# Ada_-_V1_as_built.net
KiCad netlist of a schematic drawn in EasyEDA Pro
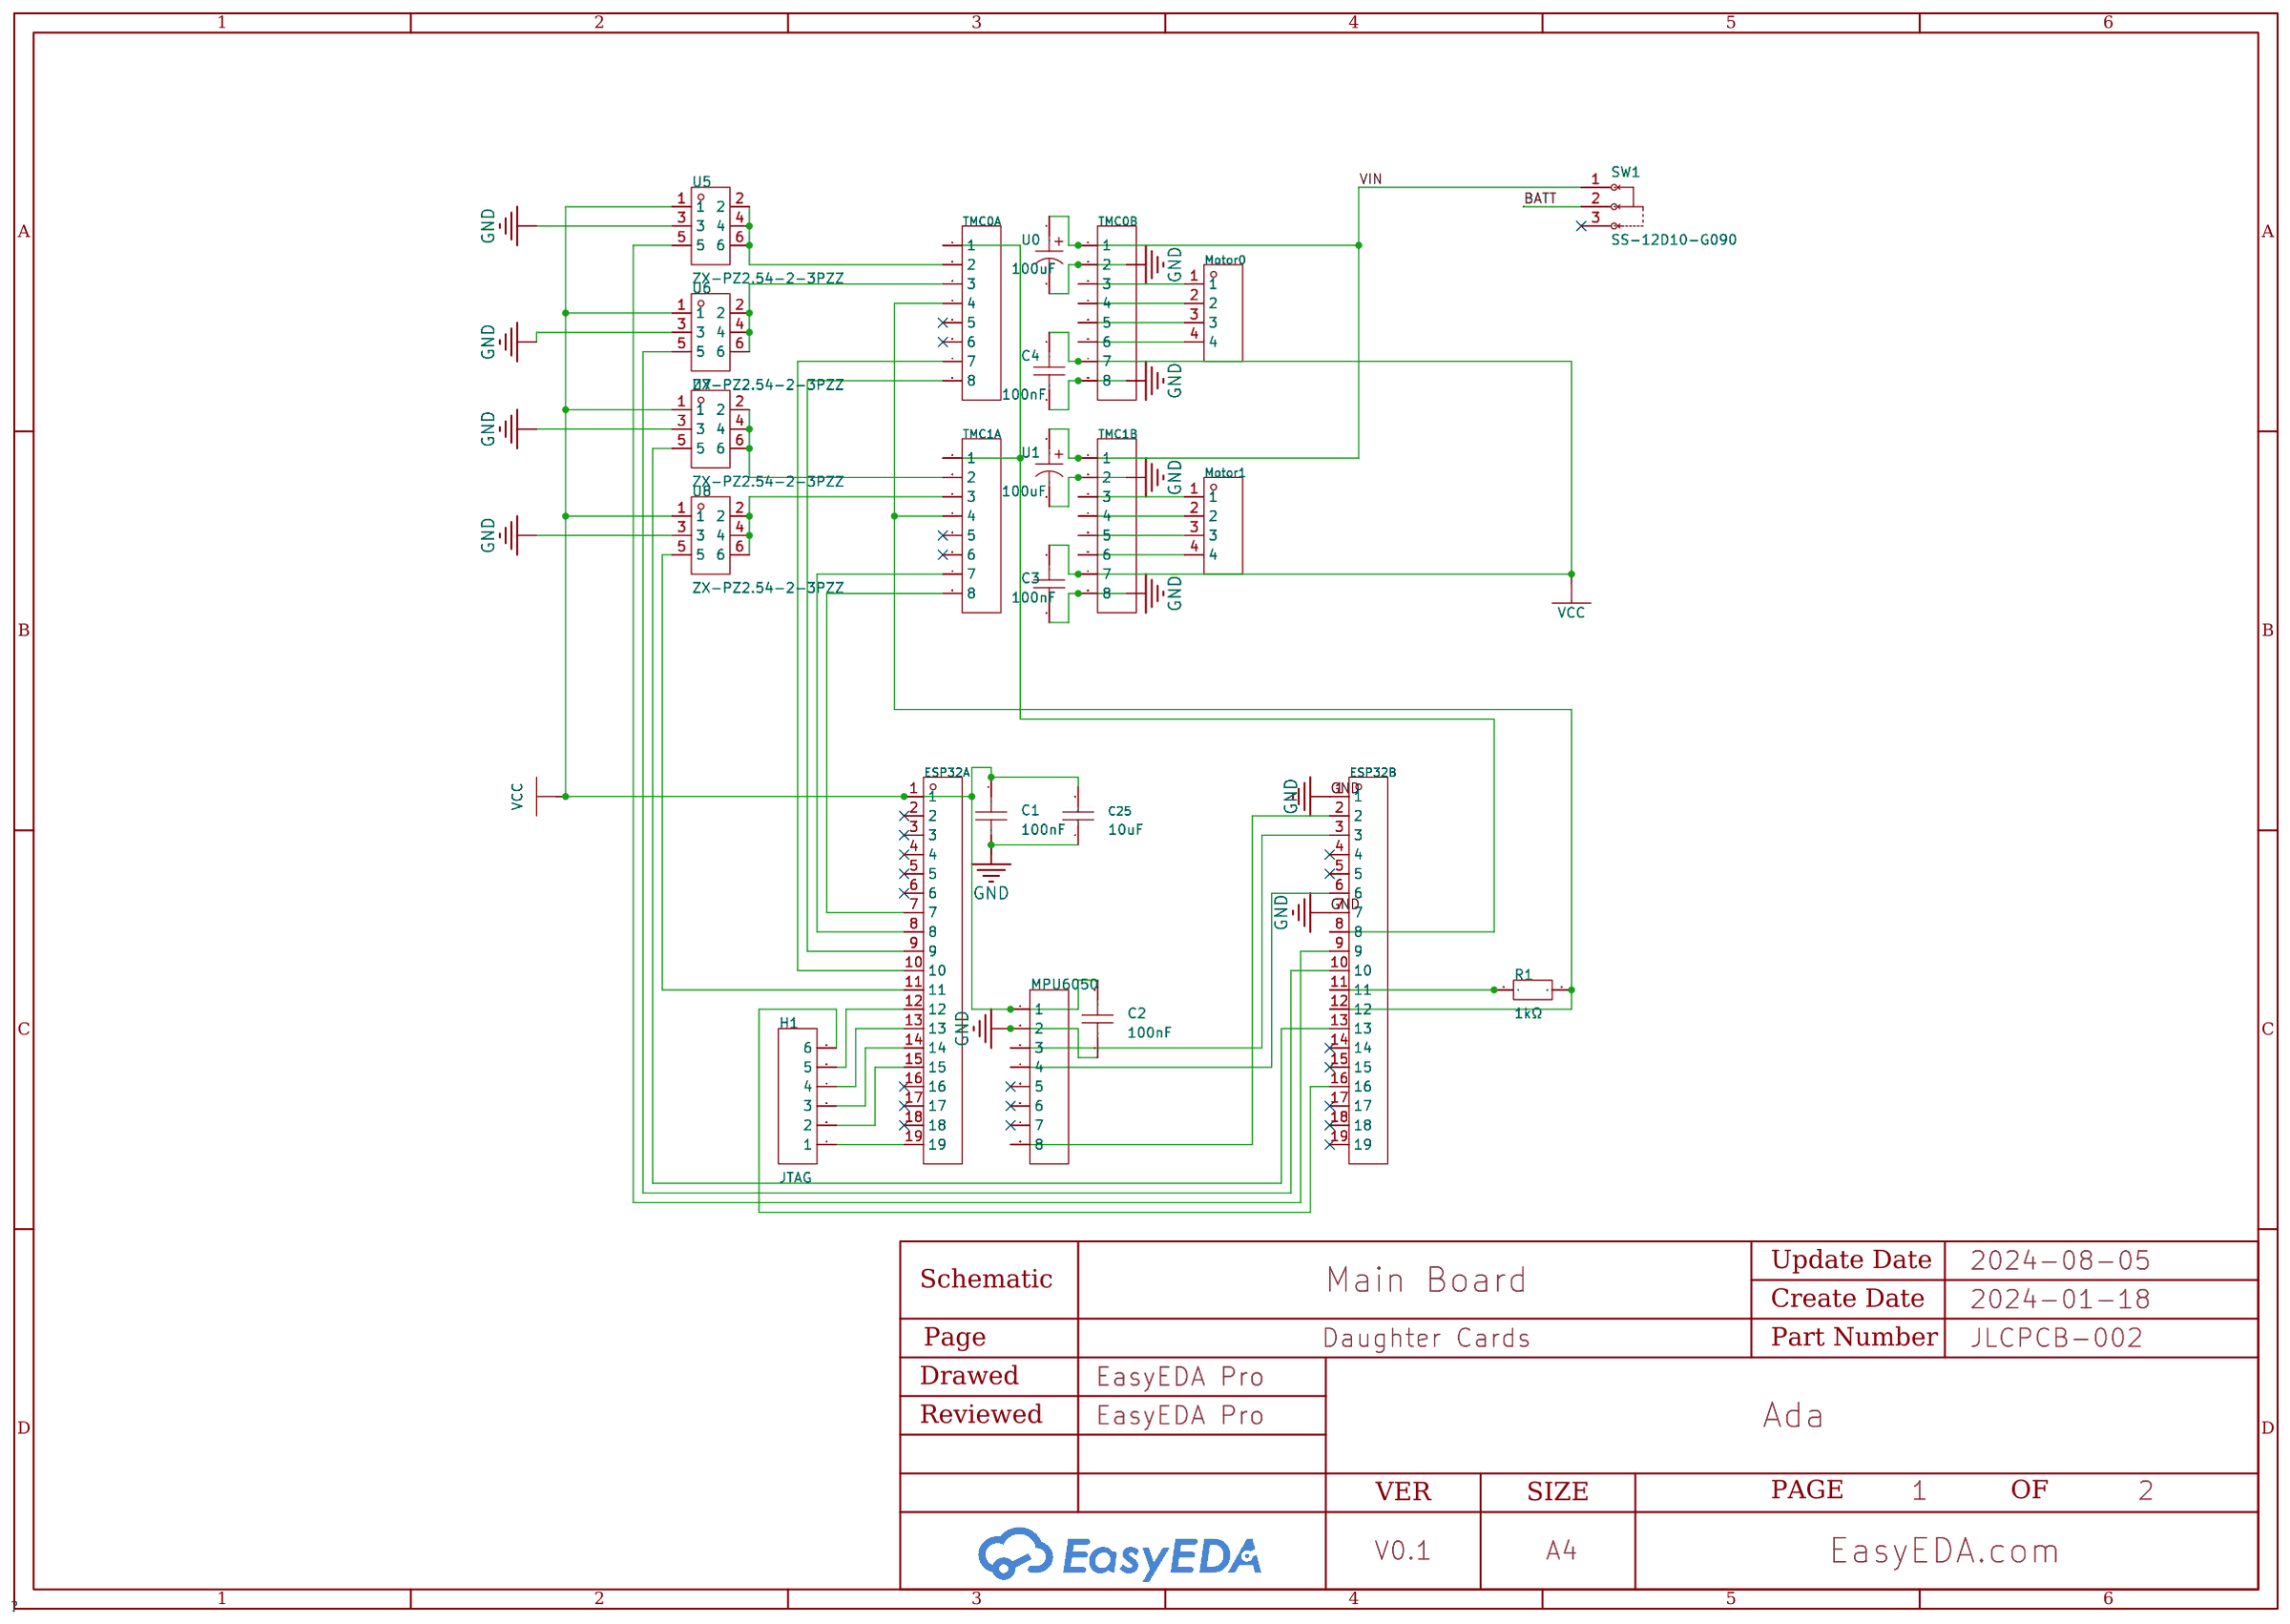
[diagram p0: Daughter Cards]
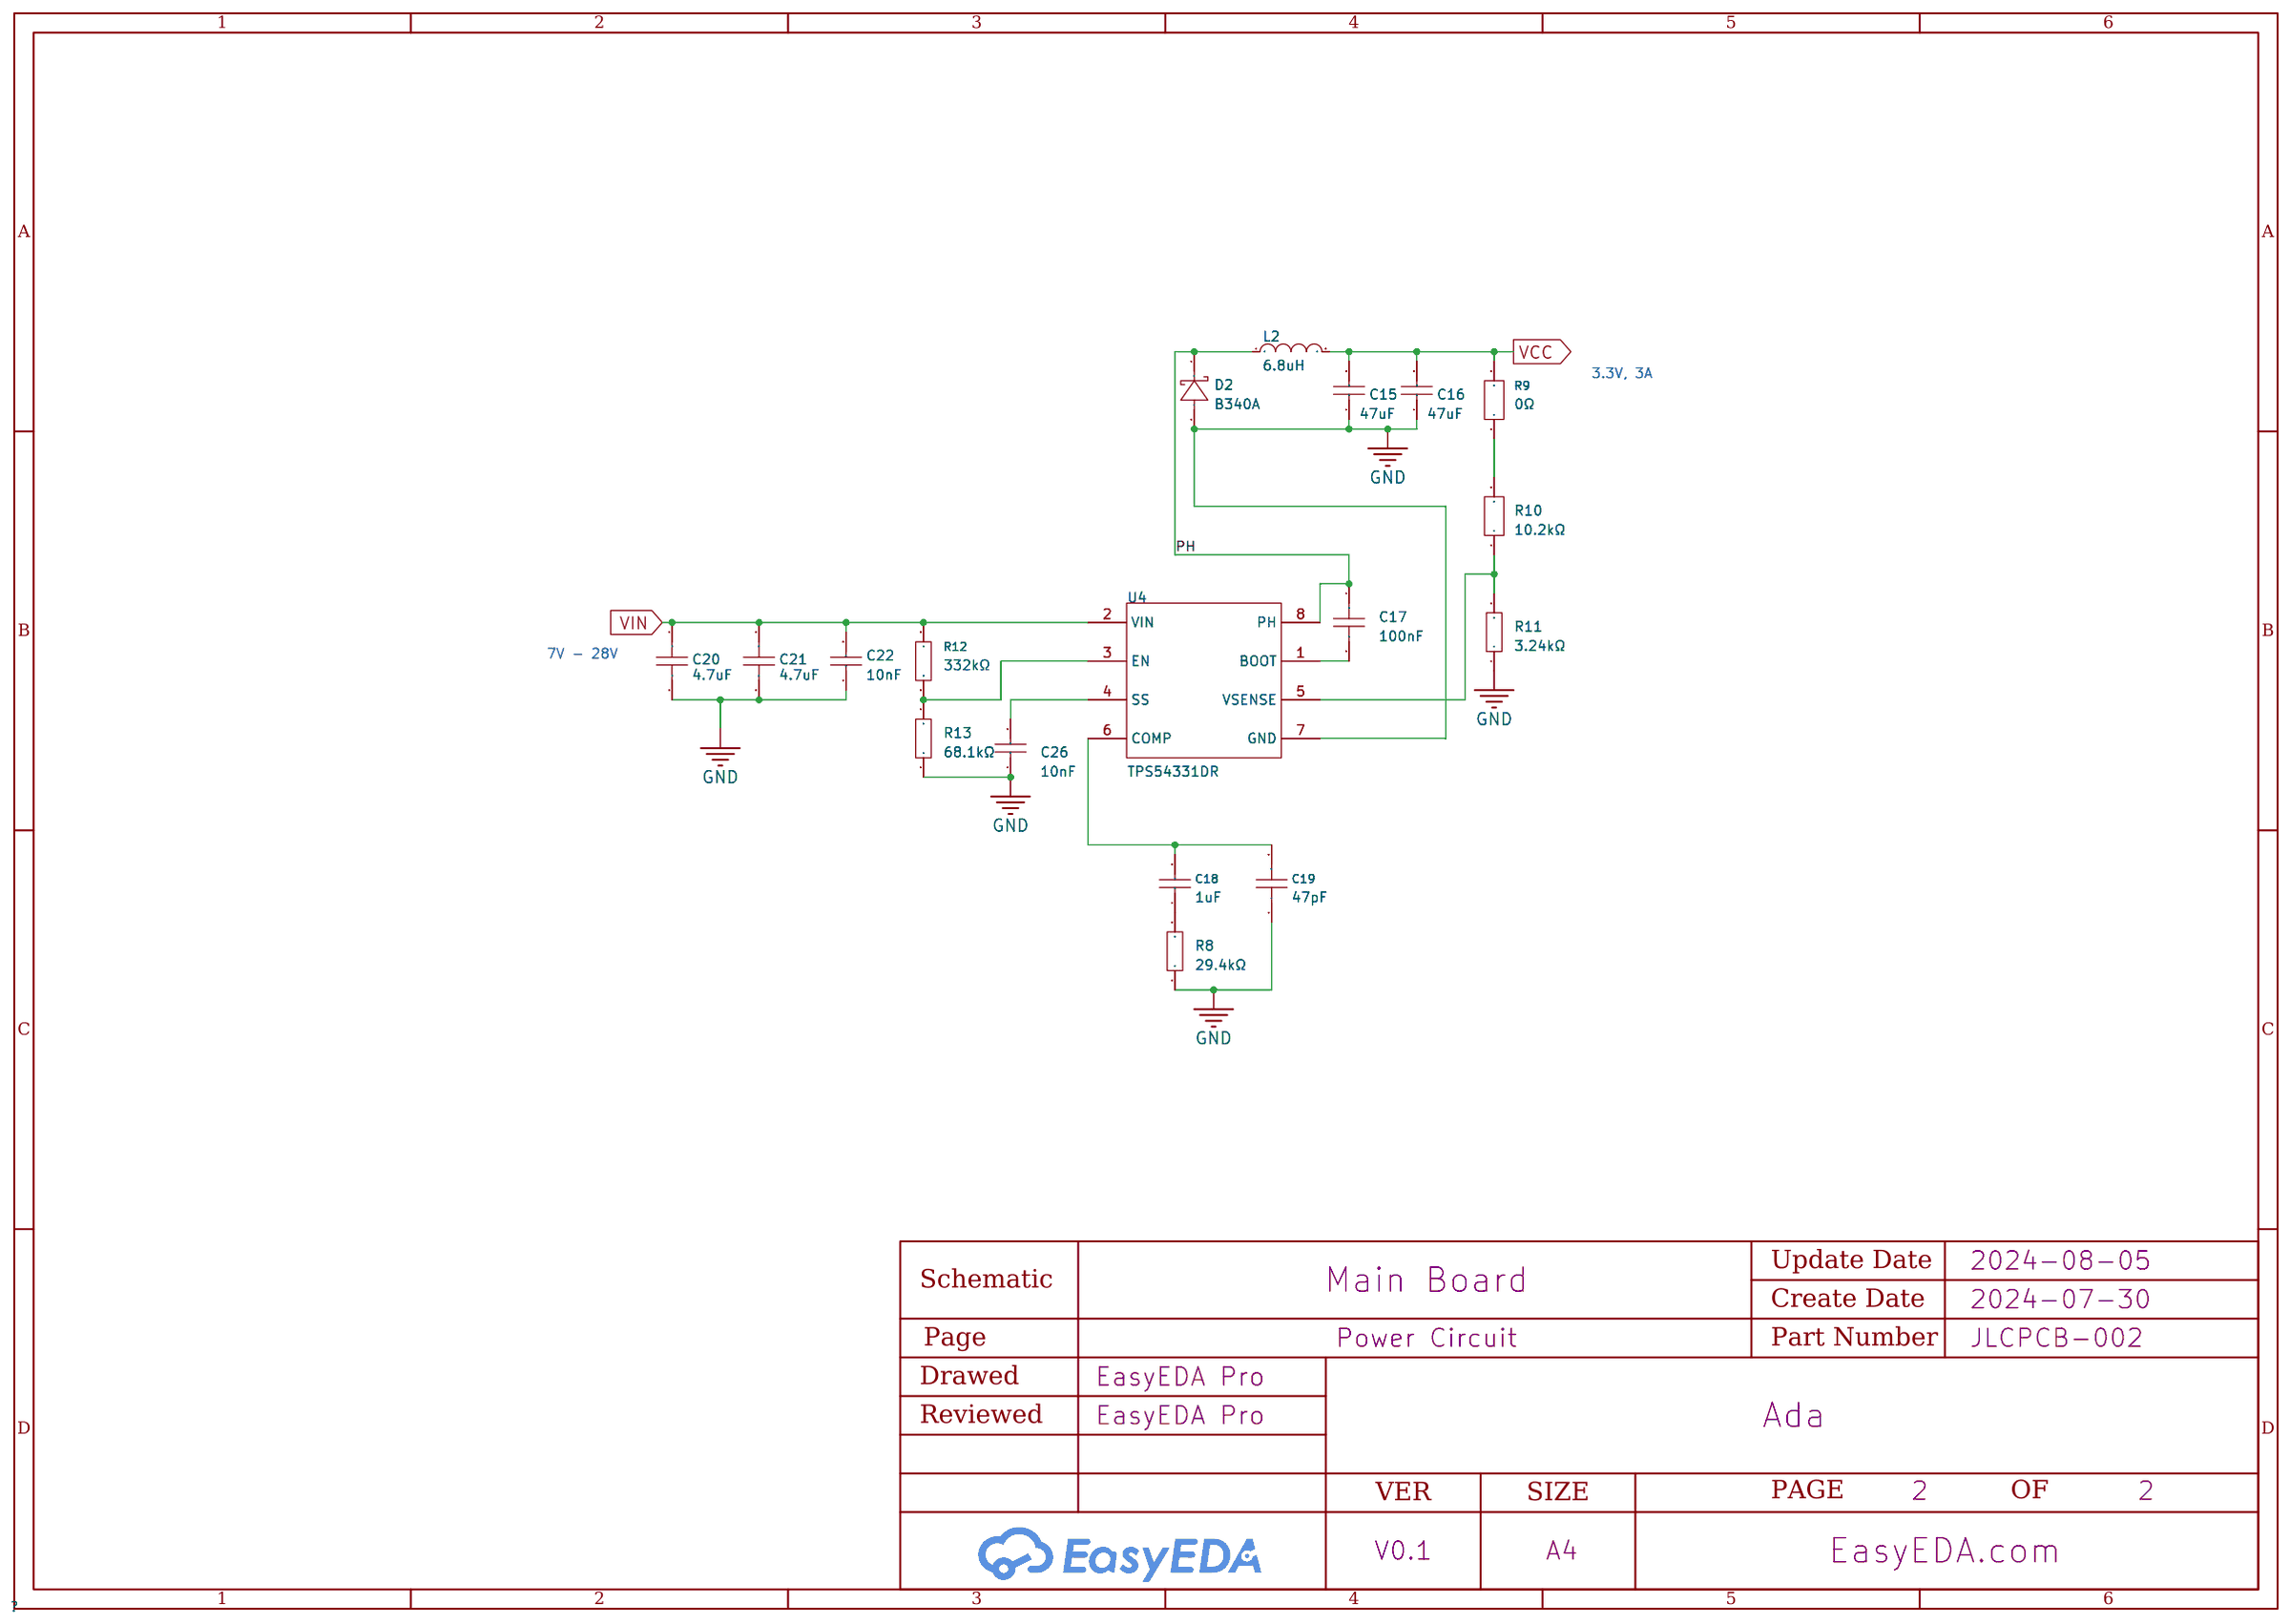
[diagram p1: Power Circuit]

(export (version "E")
  (design (tool "Eeschema 10.0.6"))
  (components
    (comp (ref "C1")
      (value "100nF")
      (footprint "easyedapro:C0201")
      (fields
        (field (name "Manufacturer Part") "CL03A104KQ3NNNC")
        (field (name "Manufacturer") "SAMSUNG(三星)")
      )
      (libsource (lib "easyedapro") (part "CL03A104KQ3NNNC"))
    )
    (comp (ref "C2")
      (value "100nF")
      (footprint "easyedapro:C0201")
      (fields
        (field (name "Manufacturer Part") "CL03A104KQ3NNNC")
        (field (name "Manufacturer") "SAMSUNG(三星)")
      )
      (libsource (lib "easyedapro") (part "CL03A104KQ3NNNC"))
    )
    (comp (ref "C3")
      (value "100nF")
      (footprint "easyedapro:C0201")
      (fields
        (field (name "Manufacturer Part") "CL03A104KQ3NNNC")
        (field (name "Manufacturer") "SAMSUNG(三星)")
      )
      (libsource (lib "easyedapro") (part "CL03A104KQ3NNNC"))
    )
    (comp (ref "C4")
      (value "100nF")
      (footprint "easyedapro:C0201")
      (fields
        (field (name "Manufacturer Part") "CL03A104KQ3NNNC")
        (field (name "Manufacturer") "SAMSUNG(三星)")
      )
      (libsource (lib "easyedapro") (part "CL03A104KQ3NNNC"))
    )
    (comp (ref "C25")
      (value "10uF")
      (footprint "easyedapro:C0402")
      (fields
        (field (name "Manufacturer Part") "CL05A106MQ5NUNC")
        (field (name "Manufacturer") "SAMSUNG(三星)")
      )
      (libsource (lib "easyedapro") (part "CL05A106MQ5NUNC"))
    )
    (comp (ref "ESP32A")
      (value "ESP32")
      (footprint "easyedapro:HDR-TH_19P-P2.54-V-F")
      (fields (field (name "Manufacturer Part") "2.54-1*19P母") (field (name "Manufacturer") "BOOMELE(博穆精密)"))
      (libsource (lib "easyedapro") (part "2.54-1*19P母"))
    )
    (comp (ref "ESP32B")
      (value "2.54-1*19P母")
      (footprint "easyedapro:HDR-TH_19P-P2.54-V-F")
      (fields (field (name "Manufacturer") "BOOMELE(博穆精密)"))
      (libsource (lib "easyedapro") (part "2.54-1*19P母"))
    )
    (comp (ref "H1")
      (value "JTAG")
      (footprint "easyedapro:HDR-TH_6P-P2.54-V-M-1")
      (fields (field (name "Manufacturer Part") "2.54-1x6P直针") (field (name "Manufacturer") "BOOMELE(博穆精密)"))
      (libsource (lib "easyedapro") (part "Header-Male-2.54_1x6"))
    )
    (comp (ref "Motor0")
      (value "Motor 0")
      (footprint "easyedapro:HDR-TH_4P-P2.54-V-M")
      (fields (field (name "Manufacturer Part") "PZ254V-11-04P") (field (name "Manufacturer") "XFCN(兴飞)"))
      (libsource (lib "easyedapro") (part "PZ254V-11-04P_C2691448"))
    )
    (comp (ref "Motor1")
      (value "Motor 1")
      (footprint "easyedapro:HDR-TH_4P-P2.54-V-M")
      (fields (field (name "Manufacturer Part") "PZ254V-11-04P") (field (name "Manufacturer") "XFCN(兴飞)"))
      (libsource (lib "easyedapro") (part "PZ254V-11-04P_C2691448"))
    )
    (comp (ref "MPU6050")
      (value "MPU6050")
      (footprint "easyedapro:HDR-TH_8P-P2.54-V-F-1")
      (fields (field (name "Manufacturer Part") "2.54-1*8P母环保") (field (name "Manufacturer") "BOOMELE(博穆精密)"))
      (libsource (lib "easyedapro") (part "Header-Female-2.54_1x8"))
    )
    (comp (ref "R1")
      (value "1kΩ")
      (footprint "easyedapro:R0603")
      (fields (field (name "Manufacturer Part") "FCR0603F1K") (field (name "Manufacturer") "VO(翔胜)"))
      (libsource (lib "easyedapro") (part "FCR0603F1K"))
    )
    (comp (ref "SW1")
      (value "SS-12D10-G090")
      (footprint "easyedapro:SW-TH_3P-L12.7-W6.6-P4.70_C9900034369")
      (fields (field (name "Manufacturer") "G-Switch(品赞)"))
      (libsource (lib "easyedapro") (part "SS-12D10-G090"))
    )
    (comp (ref "TMC0A")
      (value "TMC0A")
      (footprint "easyedapro:HDR-TH_8P-P2.54-V-F-1")
      (fields (field (name "Manufacturer Part") "2.54-1*8P母环保") (field (name "Manufacturer") "BOOMELE(博穆精密)"))
      (libsource (lib "easyedapro") (part "Header-Female-2.54_1x8"))
    )
    (comp (ref "TMC0B")
      (value "2.54-1*8P母环保")
      (footprint "easyedapro:HDR-TH_8P-P2.54-V-F-1")
      (fields (field (name "Manufacturer") "BOOMELE(博穆精密)"))
      (libsource (lib "easyedapro") (part "Header-Female-2.54_1x8"))
    )
    (comp (ref "TMC1A")
      (value "TMC2209")
      (footprint "easyedapro:HDR-TH_8P-P2.54-V-F-1")
      (fields (field (name "Manufacturer Part") "2.54-1*8P母环保") (field (name "Manufacturer") "BOOMELE(博穆精密)"))
      (libsource (lib "easyedapro") (part "Header-Female-2.54_1x8"))
    )
    (comp (ref "TMC1B")
      (value "2.54-1*8P母环保")
      (footprint "easyedapro:HDR-TH_8P-P2.54-V-F-1")
      (fields (field (name "Manufacturer") "BOOMELE(博穆精密)"))
      (libsource (lib "easyedapro") (part "Header-Female-2.54_1x8"))
    )
    (comp (ref "U0")
      (value "100uF")
      (footprint "easyedapro:CAP-TH_BD6.3-P2.50-D0.5-FD")
      (fields (field (name "Manufacturer Part") "03EC0728") (field (name "Manufacturer") "KNSCHA(科尼盛)"))
      (libsource (lib "easyedapro") (part "03EC0728"))
    )
    (comp (ref "U1")
      (value "100uF")
      (footprint "easyedapro:CAP-TH_BD6.3-P2.50-D0.5-FD")
      (fields (field (name "Manufacturer Part") "03EC0728") (field (name "Manufacturer") "KNSCHA(科尼盛)"))
      (libsource (lib "easyedapro") (part "03EC0728"))
    )
    (comp (ref "U5")
      (value "ZX-PZ2.54-2-3PZZ")
      (footprint "easyedapro:HDR-TH_6P-P2.54-V-M-R2-C3-S2.54-1")
      (fields (field (name "Manufacturer") "Megastar(兆星)"))
      (libsource (lib "easyedapro") (part "ZX-PZ2.54-2-3PZZ"))
    )
    (comp (ref "U6")
      (value "ZX-PZ2.54-2-3PZZ")
      (footprint "easyedapro:HDR-TH_6P-P2.54-V-M-R2-C3-S2.54-1")
      (fields (field (name "Manufacturer") "Megastar(兆星)"))
      (libsource (lib "easyedapro") (part "ZX-PZ2.54-2-3PZZ"))
    )
    (comp (ref "U7")
      (value "ZX-PZ2.54-2-3PZZ")
      (footprint "easyedapro:HDR-TH_6P-P2.54-V-M-R2-C3-S2.54-1")
      (fields (field (name "Manufacturer") "Megastar(兆星)"))
      (libsource (lib "easyedapro") (part "ZX-PZ2.54-2-3PZZ"))
    )
    (comp (ref "U8")
      (value "ZX-PZ2.54-2-3PZZ")
      (footprint "easyedapro:HDR-TH_6P-P2.54-V-M-R2-C3-S2.54-1")
      (fields (field (name "Manufacturer") "Megastar(兆星)"))
      (libsource (lib "easyedapro") (part "ZX-PZ2.54-2-3PZZ"))
    )
    (comp (ref "C15")
      (value "47uF")
      (footprint "easyedapro:C0805")
      (fields
        (field (name "Manufacturer Part") "CL21A476MQYNNNE")
        (field (name "Manufacturer") "SAMSUNG(三星)")
      )
      (libsource (lib "easyedapro") (part "CL21A476MQYNNNE"))
    )
    (comp (ref "C16")
      (value "47uF")
      (footprint "easyedapro:C0805")
      (fields
        (field (name "Manufacturer Part") "CL21A476MQYNNNE")
        (field (name "Manufacturer") "SAMSUNG(三星)")
      )
      (libsource (lib "easyedapro") (part "CL21A476MQYNNNE"))
    )
    (comp (ref "C17")
      (value "100nF")
      (footprint "easyedapro:C0201")
      (fields
        (field (name "Manufacturer Part") "CL03A104KQ3NNNC")
        (field (name "Manufacturer") "SAMSUNG(三星)")
      )
      (libsource (lib "easyedapro") (part "CL03A104KQ3NNNC"))
    )
    (comp (ref "C18")
      (value "1uF")
      (footprint "easyedapro:C0402")
      (fields
        (field (name "Manufacturer Part") "CL05A105KQ5NNNC")
        (field (name "Manufacturer") "SAMSUNG(三星)")
      )
      (libsource (lib "easyedapro") (part "CL05A105KQ5NNNC"))
    )
    (comp (ref "C19")
      (value "47pF")
      (footprint "easyedapro:C0603")
      (fields
        (field (name "Manufacturer Part") "CC0603JRNPO8BN470")
        (field (name "Manufacturer") "YAGEO(国巨)")
      )
      (libsource (lib "easyedapro") (part "CC0603JRNPO8BN470"))
    )
    (comp (ref "C20")
      (value "4.7uF")
      (footprint "easyedapro:C0603")
      (fields
        (field (name "Manufacturer Part") "CL10A475KL8NRNC")
        (field (name "Manufacturer") "SAMSUNG(三星)")
      )
      (libsource (lib "easyedapro") (part "CL10A475KL8NRNC"))
    )
    (comp (ref "C21")
      (value "4.7uF")
      (footprint "easyedapro:C0603")
      (fields
        (field (name "Manufacturer Part") "CL10A475KL8NRNC")
        (field (name "Manufacturer") "SAMSUNG(三星)")
      )
      (libsource (lib "easyedapro") (part "CL10A475KL8NRNC"))
    )
    (comp (ref "C22")
      (value "10nF")
      (footprint "easyedapro:C0603")
      (fields
        (field (name "Manufacturer Part") "CL10B103KB8NNNC")
        (field (name "Manufacturer") "SAMSUNG(三星)")
      )
      (libsource (lib "easyedapro") (part "CL10B103KB8NNNC"))
    )
    (comp (ref "C26")
      (value "10nF")
      (footprint "easyedapro:C0201")
      (fields
        (field (name "Manufacturer Part") "GRM033R70J103KA01D")
        (field (name "Manufacturer") "muRata(村田)")
      )
      (libsource (lib "easyedapro") (part "GRM033R70J103KA01D"))
    )
    (comp (ref "D2")
      (value "B340A")
      (footprint "easyedapro:SMA_L4.3-W2.6-LS5.0-RD")
      (fields (field (name "Manufacturer") "FUXINSEMI(富芯森美)"))
      (libsource (lib "easyedapro") (part "B340A_C3018525"))
    )
    (comp (ref "L2")
      (value "6.8uH")
      (footprint "easyedapro:IND-SMD_L5.2-W5.2_MS0530-XX")
      (fields (field (name "Manufacturer Part") "MDA5030-6R8M") (field (name "Manufacturer") "KOHERelec(科或)"))
      (libsource (lib "easyedapro") (part "MDA5030-6R8M"))
    )
    (comp (ref "R8")
      (value "29.4kΩ")
      (footprint "easyedapro:R0201")
      (fields (field (name "Manufacturer Part") "RC-01W2942FT") (field (name "Manufacturer") "FH(风华)"))
      (libsource (lib "easyedapro") (part "RC-01W2942FT"))
    )
    (comp (ref "R9")
      (value "0Ω")
      (footprint "easyedapro:R0201")
      (fields
        (field (name "Manufacturer Part") "0201WMF0000TEE")
        (field (name "Manufacturer") "UNI-ROYAL(厚声)")
      )
      (libsource (lib "easyedapro") (part "0201WMF0000TEE"))
    )
    (comp (ref "R10")
      (value "10.2kΩ")
      (footprint "easyedapro:R0201")
      (fields (field (name "Manufacturer Part") "RTT011022FTH") (field (name "Manufacturer") "RALEC(旺诠)"))
      (libsource (lib "easyedapro") (part "RTT011022FTH"))
    )
    (comp (ref "R11")
      (value "3.24kΩ")
      (footprint "easyedapro:R0603")
      (fields
        (field (name "Manufacturer Part") "0603WAF3241T5E")
        (field (name "Manufacturer") "UNI-ROYAL(厚声)")
      )
      (libsource (lib "easyedapro") (part "0603WAF3241T5E"))
    )
    (comp (ref "R12")
      (value "332kΩ")
      (footprint "easyedapro:R0402")
      (fields
        (field (name "Manufacturer Part") "0402WGF3323TCE")
        (field (name "Manufacturer") "UNI-ROYAL(厚声)")
      )
      (libsource (lib "easyedapro") (part "0402WGF3323TCE"))
    )
    (comp (ref "R13")
      (value "68.1kΩ")
      (footprint "easyedapro:R0402")
      (fields (field (name "Manufacturer Part") "AC0402FR-0768K1L") (field (name "Manufacturer") "YAGEO(国巨)"))
      (libsource (lib "easyedapro") (part "AC0402FR-0768K1L"))
    )
    (comp (ref "U4")
      (value "TPS54331DR")
      (footprint "easyedapro:SOIC-8_L5.0-W4.0-P1.27-LS6.0-BL")
      (fields (field (name "Manufacturer") "TI(德州仪器)"))
      (libsource (lib "easyedapro") (part "TPS54331DR"))
    )
  )
  (nets
    (net (code "1") (name "BATT") (class "Default")
      (node (ref "SW1") (pin "2") (pinfunction "2_2") (pintype "unspecified"))
    )
    (net (code "2") (name "GND") (class "Default")
      (node (ref "C1") (pin "2") (pinfunction "2_2") (pintype "unspecified"))
      (node (ref "C15") (pin "1") (pinfunction "1_1") (pintype "input"))
      (node (ref "C16") (pin "1") (pinfunction "1_1") (pintype "input"))
      (node (ref "C19") (pin "1") (pinfunction "1_1") (pintype "input"))
      (node (ref "C2") (pin "2") (pinfunction "2_2") (pintype "unspecified"))
      (node (ref "C20") (pin "2") (pinfunction "2_2") (pintype "unspecified"))
      (node (ref "C21") (pin "2") (pinfunction "2_2") (pintype "unspecified"))
      (node (ref "C22") (pin "1") (pinfunction "1_1") (pintype "input"))
      (node (ref "C25") (pin "1") (pinfunction "1_1") (pintype "input"))
      (node (ref "C26") (pin "1") (pinfunction "1_1") (pintype "input"))
      (node (ref "C3") (pin "2") (pinfunction "2_2") (pintype "unspecified"))
      (node (ref "C4") (pin "2") (pinfunction "2_2") (pintype "unspecified"))
      (node (ref "D2") (pin "2") (pinfunction "A_2") (pintype "unspecified"))
      (node (ref "ESP32B") (pin "1") (pinfunction "1_1") (pintype "input"))
      (node (ref "ESP32B") (pin "7") (pinfunction "7_7") (pintype "input"))
      (node (ref "MPU6050") (pin "2") (pinfunction "2_2") (pintype "input"))
      (node (ref "R11") (pin "1") (pinfunction "1_1") (pintype "input"))
      (node (ref "R13") (pin "1") (pinfunction "1_1") (pintype "unspecified"))
      (node (ref "R8") (pin "1") (pinfunction "1_1") (pintype "unspecified"))
      (node (ref "TMC0B") (pin "2") (pinfunction "2_2") (pintype "input"))
      (node (ref "TMC0B") (pin "8") (pinfunction "8_8") (pintype "input"))
      (node (ref "TMC1B") (pin "2") (pinfunction "2_2") (pintype "input"))
      (node (ref "TMC1B") (pin "8") (pinfunction "8_8") (pintype "input"))
      (node (ref "U0") (pin "2") (pinfunction "2_2") (pintype "input"))
      (node (ref "U1") (pin "2") (pinfunction "2_2") (pintype "input"))
      (node (ref "U4") (pin "7") (pinfunction "GND_7") (pintype "unspecified"))
      (node (ref "U5") (pin "3") (pinfunction "3_3") (pintype "unspecified"))
      (node (ref "U6") (pin "3") (pinfunction "3_3") (pintype "unspecified"))
      (node (ref "U7") (pin "3") (pinfunction "3_3") (pintype "unspecified"))
      (node (ref "U8") (pin "3") (pinfunction "3_3") (pintype "unspecified"))
    )
    (net (code "3") (name "Net-(C18-Pad1)") (class "Default")
      (node (ref "C18") (pin "1") (pinfunction "1_1") (pintype "input"))
      (node (ref "R8") (pin "2") (pinfunction "2_2") (pintype "unspecified"))
    )
    (net (code "4") (name "Net-(ESP32A-Pad7)") (class "Default")
      (node (ref "ESP32A") (pin "7") (pinfunction "7_7") (pintype "input"))
      (node (ref "TMC1A") (pin "8") (pinfunction "8_8") (pintype "input"))
    )
    (net (code "5") (name "Net-(ESP32A-Pad8)") (class "Default")
      (node (ref "ESP32A") (pin "8") (pinfunction "8_8") (pintype "input"))
      (node (ref "TMC1A") (pin "7") (pinfunction "7_7") (pintype "input"))
    )
    (net (code "6") (name "Net-(ESP32A-Pad9)") (class "Default")
      (node (ref "ESP32A") (pin "9") (pinfunction "9_9") (pintype "input"))
      (node (ref "TMC0A") (pin "8") (pinfunction "8_8") (pintype "input"))
    )
    (net (code "7") (name "Net-(ESP32A-Pad10)") (class "Default")
      (node (ref "ESP32A") (pin "10") (pinfunction "10_10") (pintype "input"))
      (node (ref "TMC0A") (pin "7") (pinfunction "7_7") (pintype "input"))
    )
    (net (code "8") (name "Net-(ESP32A-Pad11)") (class "Default")
      (node (ref "ESP32A") (pin "11") (pinfunction "11_11") (pintype "input"))
      (node (ref "U8") (pin "5") (pinfunction "5_5") (pintype "unspecified"))
    )
    (net (code "9") (name "Net-(ESP32A-Pad12)") (class "Default")
      (node (ref "ESP32A") (pin "12") (pinfunction "12_12") (pintype "input"))
      (node (ref "H1") (pin "5") (pinfunction "5_5") (pintype "input"))
    )
    (net (code "10") (name "Net-(ESP32A-Pad13)") (class "Default")
      (node (ref "ESP32A") (pin "13") (pinfunction "13_13") (pintype "input"))
      (node (ref "H1") (pin "4") (pinfunction "4_4") (pintype "input"))
    )
    (net (code "11") (name "Net-(ESP32A-Pad14)") (class "Default")
      (node (ref "ESP32A") (pin "14") (pinfunction "14_14") (pintype "input"))
      (node (ref "H1") (pin "3") (pinfunction "3_3") (pintype "input"))
    )
    (net (code "12") (name "Net-(ESP32A-Pad15)") (class "Default")
      (node (ref "ESP32A") (pin "15") (pinfunction "15_15") (pintype "input"))
      (node (ref "H1") (pin "2") (pinfunction "2_2") (pintype "input"))
    )
    (net (code "13") (name "Net-(ESP32A-Pad19)") (class "Default")
      (node (ref "ESP32A") (pin "19") (pinfunction "19_19") (pintype "input"))
      (node (ref "H1") (pin "1") (pinfunction "1_1") (pintype "input"))
    )
    (net (code "14") (name "Net-(ESP32B-Pad2)") (class "Default")
      (node (ref "ESP32B") (pin "2") (pinfunction "2_2") (pintype "input"))
      (node (ref "MPU6050") (pin "8") (pinfunction "8_8") (pintype "input"))
    )
    (net (code "15") (name "Net-(ESP32B-Pad3)") (class "Default")
      (node (ref "ESP32B") (pin "3") (pinfunction "3_3") (pintype "input"))
      (node (ref "MPU6050") (pin "3") (pinfunction "3_3") (pintype "input"))
    )
    (net (code "16") (name "Net-(ESP32B-Pad6)") (class "Default")
      (node (ref "ESP32B") (pin "6") (pinfunction "6_6") (pintype "input"))
      (node (ref "MPU6050") (pin "4") (pinfunction "4_4") (pintype "input"))
    )
    (net (code "17") (name "Net-(ESP32B-Pad8)") (class "Default")
      (node (ref "ESP32B") (pin "8") (pinfunction "8_8") (pintype "input"))
      (node (ref "TMC0A") (pin "1") (pinfunction "1_1") (pintype "input"))
      (node (ref "TMC1A") (pin "1") (pinfunction "1_1") (pintype "input"))
    )
    (net (code "18") (name "Net-(ESP32B-Pad9)") (class "Default")
      (node (ref "ESP32B") (pin "9") (pinfunction "9_9") (pintype "input"))
      (node (ref "U5") (pin "5") (pinfunction "5_5") (pintype "unspecified"))
    )
    (net (code "19") (name "Net-(ESP32B-Pad10)") (class "Default")
      (node (ref "ESP32B") (pin "10") (pinfunction "10_10") (pintype "input"))
      (node (ref "U6") (pin "5") (pinfunction "5_5") (pintype "unspecified"))
    )
    (net (code "20") (name "Net-(ESP32B-Pad11)") (class "Default")
      (node (ref "ESP32B") (pin "11") (pinfunction "11_11") (pintype "input"))
      (node (ref "R1") (pin "1") (pinfunction "1_1") (pintype "unspecified"))
    )
    (net (code "21") (name "Net-(ESP32B-Pad12)") (class "Default")
      (node (ref "ESP32B") (pin "12") (pinfunction "12_12") (pintype "input"))
      (node (ref "R1") (pin "2") (pinfunction "2_2") (pintype "unspecified"))
      (node (ref "TMC0A") (pin "4") (pinfunction "4_4") (pintype "input"))
      (node (ref "TMC1A") (pin "4") (pinfunction "4_4") (pintype "input"))
    )
    (net (code "22") (name "Net-(ESP32B-Pad13)") (class "Default")
      (node (ref "ESP32B") (pin "13") (pinfunction "13_13") (pintype "input"))
      (node (ref "U7") (pin "5") (pinfunction "5_5") (pintype "unspecified"))
    )
    (net (code "23") (name "Net-(ESP32B-Pad16)") (class "Default")
      (node (ref "ESP32B") (pin "16") (pinfunction "16_16") (pintype "input"))
      (node (ref "H1") (pin "6") (pinfunction "6_6") (pintype "input"))
    )
    (net (code "24") (name "Net-(Motor0-Pad1)") (class "Default")
      (node (ref "Motor0") (pin "1") (pinfunction "1_1") (pintype "input"))
      (node (ref "TMC0B") (pin "3") (pinfunction "3_3") (pintype "input"))
    )
    (net (code "25") (name "Net-(Motor0-Pad2)") (class "Default")
      (node (ref "Motor0") (pin "2") (pinfunction "2_2") (pintype "input"))
      (node (ref "TMC0B") (pin "4") (pinfunction "4_4") (pintype "input"))
    )
    (net (code "26") (name "Net-(Motor0-Pad3)") (class "Default")
      (node (ref "Motor0") (pin "3") (pinfunction "3_3") (pintype "input"))
      (node (ref "TMC0B") (pin "5") (pinfunction "5_5") (pintype "input"))
    )
    (net (code "27") (name "Net-(Motor0-Pad4)") (class "Default")
      (node (ref "Motor0") (pin "4") (pinfunction "4_4") (pintype "input"))
      (node (ref "TMC0B") (pin "6") (pinfunction "6_6") (pintype "input"))
    )
    (net (code "28") (name "Net-(Motor1-Pad1)") (class "Default")
      (node (ref "Motor1") (pin "1") (pinfunction "1_1") (pintype "input"))
      (node (ref "TMC1B") (pin "3") (pinfunction "3_3") (pintype "input"))
    )
    (net (code "29") (name "Net-(Motor1-Pad2)") (class "Default")
      (node (ref "Motor1") (pin "2") (pinfunction "2_2") (pintype "input"))
      (node (ref "TMC1B") (pin "4") (pinfunction "4_4") (pintype "input"))
    )
    (net (code "30") (name "Net-(Motor1-Pad3)") (class "Default")
      (node (ref "Motor1") (pin "3") (pinfunction "3_3") (pintype "input"))
      (node (ref "TMC1B") (pin "5") (pinfunction "5_5") (pintype "input"))
    )
    (net (code "31") (name "Net-(Motor1-Pad4)") (class "Default")
      (node (ref "Motor1") (pin "4") (pinfunction "4_4") (pintype "input"))
      (node (ref "TMC1B") (pin "6") (pinfunction "6_6") (pintype "input"))
    )
    (net (code "32") (name "Net-(R10-Pad2)") (class "Default")
      (node (ref "R10") (pin "2") (pinfunction "2_2") (pintype "unspecified"))
      (node (ref "R9") (pin "1") (pinfunction "1_1") (pintype "input"))
    )
    (net (code "33") (name "Net-(TMC0A-Pad2)") (class "Default")
      (node (ref "TMC0A") (pin "2") (pinfunction "2_2") (pintype "input"))
      (node (ref "U5") (pin "2") (pinfunction "2_2") (pintype "unspecified"))
      (node (ref "U5") (pin "4") (pinfunction "4_4") (pintype "unspecified"))
      (node (ref "U5") (pin "6") (pinfunction "6_6") (pintype "unspecified"))
    )
    (net (code "34") (name "Net-(TMC0A-Pad3)") (class "Default")
      (node (ref "TMC0A") (pin "3") (pinfunction "3_3") (pintype "input"))
      (node (ref "U6") (pin "2") (pinfunction "2_2") (pintype "unspecified"))
      (node (ref "U6") (pin "4") (pinfunction "4_4") (pintype "unspecified"))
      (node (ref "U6") (pin "6") (pinfunction "6_6") (pintype "unspecified"))
    )
    (net (code "35") (name "Net-(TMC1A-Pad2)") (class "Default")
      (node (ref "TMC1A") (pin "2") (pinfunction "2_2") (pintype "input"))
      (node (ref "U7") (pin "2") (pinfunction "2_2") (pintype "unspecified"))
      (node (ref "U7") (pin "4") (pinfunction "4_4") (pintype "unspecified"))
      (node (ref "U7") (pin "6") (pinfunction "6_6") (pintype "unspecified"))
    )
    (net (code "36") (name "Net-(TMC1A-Pad3)") (class "Default")
      (node (ref "TMC1A") (pin "3") (pinfunction "3_3") (pintype "input"))
      (node (ref "U8") (pin "2") (pinfunction "2_2") (pintype "unspecified"))
      (node (ref "U8") (pin "4") (pinfunction "4_4") (pintype "unspecified"))
      (node (ref "U8") (pin "6") (pinfunction "6_6") (pintype "unspecified"))
    )
    (net (code "37") (name "Net-(U4-BOOT)") (class "Default")
      (node (ref "C17") (pin "2") (pinfunction "2_2") (pintype "unspecified"))
      (node (ref "U4") (pin "1") (pinfunction "BOOT_1") (pintype "unspecified"))
    )
    (net (code "38") (name "Net-(U4-COMP)") (class "Default")
      (node (ref "C18") (pin "2") (pinfunction "2_2") (pintype "input"))
      (node (ref "C19") (pin "2") (pinfunction "2_2") (pintype "input"))
      (node (ref "U4") (pin "6") (pinfunction "COMP_6") (pintype "unspecified"))
    )
    (net (code "39") (name "Net-(U4-EN)") (class "Default")
      (node (ref "R12") (pin "1") (pinfunction "1_1") (pintype "input"))
      (node (ref "R13") (pin "2") (pinfunction "2_2") (pintype "unspecified"))
      (node (ref "U4") (pin "3") (pinfunction "EN_3") (pintype "unspecified"))
    )
    (net (code "40") (name "Net-(U4-SS)") (class "Default")
      (node (ref "C26") (pin "2") (pinfunction "2_2") (pintype "input"))
      (node (ref "U4") (pin "4") (pinfunction "SS_4") (pintype "unspecified"))
    )
    (net (code "41") (name "Net-(U4-VSENSE)") (class "Default")
      (node (ref "R10") (pin "1") (pinfunction "1_1") (pintype "unspecified"))
      (node (ref "R11") (pin "2") (pinfunction "2_2") (pintype "input"))
      (node (ref "U4") (pin "5") (pinfunction "VSENSE_5") (pintype "unspecified"))
    )
    (net (code "42") (name "PH") (class "Default")
      (node (ref "C17") (pin "1") (pinfunction "1_1") (pintype "unspecified"))
      (node (ref "D2") (pin "1") (pinfunction "K_1") (pintype "unspecified"))
      (node (ref "L2") (pin "1") (pinfunction "1_1") (pintype "unspecified"))
      (node (ref "U4") (pin "8") (pinfunction "PH_8") (pintype "unspecified"))
    )
    (net (code "43") (name "VCC") (class "Default")
      (node (ref "C1") (pin "1") (pinfunction "1_1") (pintype "unspecified"))
      (node (ref "C15") (pin "2") (pinfunction "2_2") (pintype "input"))
      (node (ref "C16") (pin "2") (pinfunction "2_2") (pintype "input"))
      (node (ref "C2") (pin "1") (pinfunction "1_1") (pintype "unspecified"))
      (node (ref "C25") (pin "2") (pinfunction "2_2") (pintype "input"))
      (node (ref "C3") (pin "1") (pinfunction "1_1") (pintype "unspecified"))
      (node (ref "C4") (pin "1") (pinfunction "1_1") (pintype "unspecified"))
      (node (ref "ESP32A") (pin "1") (pinfunction "1_1") (pintype "input"))
      (node (ref "L2") (pin "2") (pinfunction "2_2") (pintype "unspecified"))
      (node (ref "MPU6050") (pin "1") (pinfunction "1_1") (pintype "input"))
      (node (ref "R9") (pin "2") (pinfunction "2_2") (pintype "input"))
      (node (ref "TMC0B") (pin "7") (pinfunction "7_7") (pintype "input"))
      (node (ref "TMC1B") (pin "7") (pinfunction "7_7") (pintype "input"))
      (node (ref "U5") (pin "1") (pinfunction "1_1") (pintype "unspecified"))
      (node (ref "U6") (pin "1") (pinfunction "1_1") (pintype "unspecified"))
      (node (ref "U7") (pin "1") (pinfunction "1_1") (pintype "unspecified"))
      (node (ref "U8") (pin "1") (pinfunction "1_1") (pintype "unspecified"))
    )
    (net (code "44") (name "VIN") (class "Default")
      (node (ref "C20") (pin "1") (pinfunction "1_1") (pintype "unspecified"))
      (node (ref "C21") (pin "1") (pinfunction "1_1") (pintype "unspecified"))
      (node (ref "C22") (pin "2") (pinfunction "2_2") (pintype "input"))
      (node (ref "R12") (pin "2") (pinfunction "2_2") (pintype "input"))
      (node (ref "SW1") (pin "1") (pinfunction "1_1") (pintype "unspecified"))
      (node (ref "TMC0B") (pin "1") (pinfunction "1_1") (pintype "input"))
      (node (ref "TMC1B") (pin "1") (pinfunction "1_1") (pintype "input"))
      (node (ref "U0") (pin "1") (pinfunction "1_1") (pintype "input"))
      (node (ref "U1") (pin "1") (pinfunction "1_1") (pintype "input"))
      (node (ref "U4") (pin "2") (pinfunction "VIN_2") (pintype "unspecified"))
    )
    (net (code "45") (name "unconnected-(ESP32A-Pad2)") (class "Default")
      (node (ref "ESP32A") (pin "2") (pinfunction "2_2") (pintype "input+no_connect"))
    )
    (net (code "46") (name "unconnected-(ESP32A-Pad3)") (class "Default")
      (node (ref "ESP32A") (pin "3") (pinfunction "3_3") (pintype "input+no_connect"))
    )
    (net (code "47") (name "unconnected-(ESP32A-Pad4)") (class "Default")
      (node (ref "ESP32A") (pin "4") (pinfunction "4_4") (pintype "input+no_connect"))
    )
    (net (code "48") (name "unconnected-(ESP32A-Pad5)") (class "Default")
      (node (ref "ESP32A") (pin "5") (pinfunction "5_5") (pintype "input+no_connect"))
    )
    (net (code "49") (name "unconnected-(ESP32A-Pad6)") (class "Default")
      (node (ref "ESP32A") (pin "6") (pinfunction "6_6") (pintype "input+no_connect"))
    )
    (net (code "50") (name "unconnected-(ESP32A-Pad16)") (class "Default")
      (node (ref "ESP32A") (pin "16") (pinfunction "16_16") (pintype "input+no_connect"))
    )
    (net (code "51") (name "unconnected-(ESP32A-Pad17)") (class "Default")
      (node (ref "ESP32A") (pin "17") (pinfunction "17_17") (pintype "input+no_connect"))
    )
    (net (code "52") (name "unconnected-(ESP32A-Pad18)") (class "Default")
      (node (ref "ESP32A") (pin "18") (pinfunction "18_18") (pintype "input+no_connect"))
    )
    (net (code "53") (name "unconnected-(ESP32B-Pad4)") (class "Default")
      (node (ref "ESP32B") (pin "4") (pinfunction "4_4") (pintype "input+no_connect"))
    )
    (net (code "54") (name "unconnected-(ESP32B-Pad5)") (class "Default")
      (node (ref "ESP32B") (pin "5") (pinfunction "5_5") (pintype "input+no_connect"))
    )
    (net (code "55") (name "unconnected-(ESP32B-Pad14)") (class "Default")
      (node (ref "ESP32B") (pin "14") (pinfunction "14_14") (pintype "input+no_connect"))
    )
    (net (code "56") (name "unconnected-(ESP32B-Pad15)") (class "Default")
      (node (ref "ESP32B") (pin "15") (pinfunction "15_15") (pintype "input+no_connect"))
    )
    (net (code "57") (name "unconnected-(ESP32B-Pad17)") (class "Default")
      (node (ref "ESP32B") (pin "17") (pinfunction "17_17") (pintype "input+no_connect"))
    )
    (net (code "58") (name "unconnected-(ESP32B-Pad18)") (class "Default")
      (node (ref "ESP32B") (pin "18") (pinfunction "18_18") (pintype "input+no_connect"))
    )
    (net (code "59") (name "unconnected-(ESP32B-Pad19)") (class "Default")
      (node (ref "ESP32B") (pin "19") (pinfunction "19_19") (pintype "input+no_connect"))
    )
    (net (code "60") (name "unconnected-(MPU6050-Pad5)") (class "Default")
      (node (ref "MPU6050") (pin "5") (pinfunction "5_5") (pintype "input+no_connect"))
    )
    (net (code "61") (name "unconnected-(MPU6050-Pad6)") (class "Default")
      (node (ref "MPU6050") (pin "6") (pinfunction "6_6") (pintype "input+no_connect"))
    )
    (net (code "62") (name "unconnected-(MPU6050-Pad7)") (class "Default")
      (node (ref "MPU6050") (pin "7") (pinfunction "7_7") (pintype "input+no_connect"))
    )
    (net (code "63") (name "unconnected-(SW1-Pad3)") (class "Default")
      (node (ref "SW1") (pin "3") (pinfunction "3_3") (pintype "unspecified+no_connect"))
    )
    (net (code "64") (name "unconnected-(TMC0A-Pad5)") (class "Default")
      (node (ref "TMC0A") (pin "5") (pinfunction "5_5") (pintype "input+no_connect"))
    )
    (net (code "65") (name "unconnected-(TMC0A-Pad6)") (class "Default")
      (node (ref "TMC0A") (pin "6") (pinfunction "6_6") (pintype "input+no_connect"))
    )
    (net (code "66") (name "unconnected-(TMC1A-Pad5)") (class "Default")
      (node (ref "TMC1A") (pin "5") (pinfunction "5_5") (pintype "input+no_connect"))
    )
    (net (code "67") (name "unconnected-(TMC1A-Pad6)") (class "Default")
      (node (ref "TMC1A") (pin "6") (pinfunction "6_6") (pintype "input+no_connect"))
    )
  )
)
